# PTFV_GECKO_SNSR.net
KiCad netlist of a schematic drawn in Altium Designer
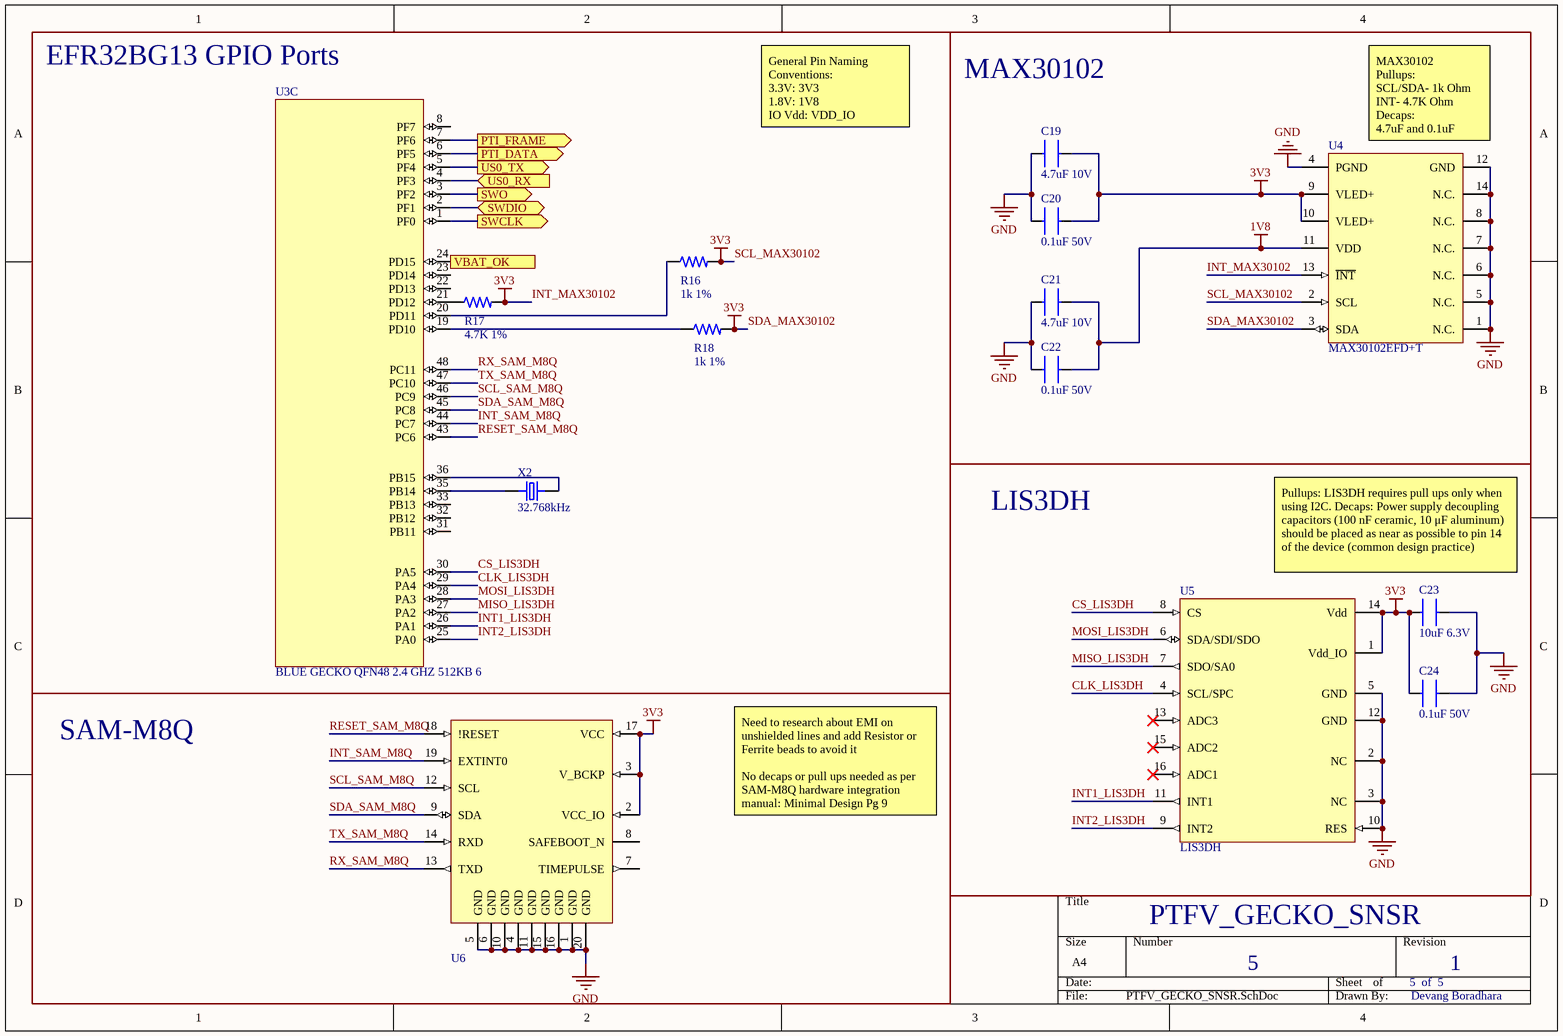
[diagram p0: PTFV_GECKO_SNSR.SchDoc]

(export (version "E")
  (design (tool "Eeschema 10.0.6"))
  (components
    (comp (ref "C19")
      (value "4.7uF 10V")
      (footprint "CAP_0603_1MM")
      (description "CAP CER 4.7UF 10V X5R 0603")
      (fields
        (field (name "MANUFACTURER") "Samsung")
        (field (name "MANUFACTURER PART NUMBER") "CL10A475KP8NNNC")
      )
      (libsource (lib "LPEDT_Parts") (part "CL10A475KP8NNNC"))
    )
    (comp (ref "C20")
      (value "0.1uF 50V")
      (footprint "CAP_0603_1MM")
      (description "CAP CER 0.1UF 50V X5R 0603")
      (fields
        (field (name "MANUFACTURER") "Yageo")
        (field (name "MANUFACTURER PART NUMBER") "CC0603KRX5R9BB104")
      )
      (libsource (lib "LPEDT_Parts") (part "CC0603KRX5R9BB104"))
    )
    (comp (ref "C21")
      (value "4.7uF 10V")
      (footprint "CAP_0603_1MM")
      (description "CAP CER 4.7UF 10V X5R 0603")
      (fields
        (field (name "MANUFACTURER") "Samsung")
        (field (name "MANUFACTURER PART NUMBER") "CL10A475KP8NNNC")
      )
      (libsource (lib "LPEDT_Parts") (part "CL10A475KP8NNNC"))
    )
    (comp (ref "C22")
      (value "0.1uF 50V")
      (footprint "CAP_0603_1MM")
      (description "CAP CER 0.1UF 50V X5R 0603")
      (fields
        (field (name "MANUFACTURER") "Yageo")
        (field (name "MANUFACTURER PART NUMBER") "CC0603KRX5R9BB104")
      )
      (libsource (lib "LPEDT_Parts") (part "CC0603KRX5R9BB104"))
    )
    (comp (ref "C23")
      (value "10uF 6.3V")
      (footprint "CAP_0603_1MM")
      (description "CAP CER 10UF 6.3V X5R 0603")
      (fields
        (field (name "MANUFACTURER") "Samsung")
        (field (name "MANUFACTURER PART NUMBER") "CL10A106MQ8NNNC")
      )
      (libsource (lib "LPEDT_Parts") (part "CL10A106MQ8NNNC"))
    )
    (comp (ref "C24")
      (value "0.1uF 50V")
      (footprint "CAP_0603_1MM")
      (description "CAP CER 0.1UF 50V X5R 0603")
      (fields
        (field (name "MANUFACTURER") "Yageo")
        (field (name "MANUFACTURER PART NUMBER") "CC0603KRX5R9BB104")
      )
      (libsource (lib "LPEDT_Parts") (part "CC0603KRX5R9BB104"))
    )
    (comp (ref "R16")
      (value "1k 1%")
      (footprint "RES_0603_1608X06")
      (description "RES SMD 1k OHM 1% 1/10W 0603")
      (fields
        (field (name "MANUFACTURER") "Yageo")
        (field (name "MANUFACTURER PART NUMBER") "RC0603FR-071KL")
      )
      (libsource (lib "LPEDT_Parts_Library") (part "RC0603FR-071KL"))
    )
    (comp (ref "R17")
      (value "4.7K 1%")
      (footprint "RES_0603_1608X06")
      (description "RES SMD 4.7K OHM 1% 1/10W 0603")
      (fields
        (field (name "MANUFACTURER") "Stackpole Electronics")
        (field (name "MANUFACTURER PART NUMBER") "RMCF0603FT4K70")
      )
      (libsource (lib "LPEDT_Parts_Library") (part "RMCF0603FT4K70"))
    )
    (comp (ref "R18")
      (value "1k 1%")
      (footprint "RES_0603_1608X06")
      (description "RES SMD 1k OHM 1% 1/10W 0603")
      (fields
        (field (name "MANUFACTURER") "Yageo")
        (field (name "MANUFACTURER PART NUMBER") "RC0603FR-071KL")
      )
      (libsource (lib "LPEDT_Parts_Library") (part "RC0603FR-071KL"))
    )
    (comp (ref "U3")
      (value "BLUE GECKO QFN48 2.4 GHZ 512KB 6")
      (footprint "QFN_48_7X7")
      (description "Blue Gecko BLE Soc QFN48 2.4 G 10 dB BLE/Proprietary 512 kB 64 kB(RAM) 31GPIO")
      (fields
        (field (name "MANUFACTURER") "Silicon Labs")
        (field (name "MANUFACTURER PART NUMBER") "EFR32BG13P632F512GM48-DR")
      )
      (libsource (lib "LPEDT_Parts_Library") (part "EFR32BG13P632F512GM48-DR"))
    )
    (comp (ref "U4")
      (value "MAX30102EFD+T")
      (footprint "14_SON_SPO2")
      (description "SENSOR OXIMETER/HEART RATE I2C")
      (fields (field (name "MANUFACTURER") "Maxim"))
      (libsource (lib "LPEDT_Parts") (part "MAX30102EFD+T"))
    )
    (comp (ref "U5")
      (value "LIS3DH")
      (footprint "16_QFN_LIS3DH")
      (libsource (lib "LPEDT_Parts_Library") (part "LIS3DH"))
    )
    (comp (ref "U6")
      (value "GPS_SAM-M8Q")
      (footprint "20_QFN_SAM_M8Q")
      (description "RF Receiver Galileo, GLONASS, GPS 1.575GHz, 1.602GHz -165dBm 400kbps On-Board, Patch Module")
      (fields (field (name "MANUFACTURER") "u-blox") (field (name "MANUFACTURER PART NUMBER") "SAM-M8Q-0"))
      (libsource (lib "LPEDT_Parts_Library") (part "SAM-M8Q-0-10"))
    )
    (comp (ref "X2")
      (value "32.768kHz")
      (footprint "XTAL_ECS-.327-7-34B-TR")
      (description "32.768kHz Â±20ppm Crystal 7pF 70 kOhms 2-SMD, No Lead")
      (fields (field (name "MP") "ECS-.327-7-34B-TR") (field (name "MF") "ECS Inc."))
      (libsource (lib "LPEDT_Parts_Library") (part "ECS-.327-7-34B-TR"))
    )
  )
  (nets
    (net (code "1") (name "/CLK_LIS3DH") (class "Default")
      (node (ref "U3") (pin "29") (pinfunction "PA4_29") (pintype "bidirectional"))
      (node (ref "U5") (pin "4") (pinfunction "SCL/SPC_4") (pintype "input"))
    )
    (net (code "2") (name "/CS_LIS3DH") (class "Default")
      (node (ref "U3") (pin "30") (pinfunction "PA5_30") (pintype "bidirectional"))
      (node (ref "U5") (pin "8") (pinfunction "CS_8") (pintype "input"))
    )
    (net (code "3") (name "/INT1_LIS3DH") (class "Default")
      (node (ref "U3") (pin "26") (pinfunction "PA1_26") (pintype "bidirectional"))
      (node (ref "U5") (pin "11") (pinfunction "INT1_11") (pintype "output"))
    )
    (net (code "4") (name "/INT2_LIS3DH") (class "Default")
      (node (ref "U3") (pin "25") (pinfunction "PA0_25") (pintype "bidirectional"))
      (node (ref "U5") (pin "9") (pinfunction "INT2_9") (pintype "output"))
    )
    (net (code "5") (name "/INT_SAM_M8Q") (class "Default")
      (node (ref "U3") (pin "44") (pinfunction "PC7_44") (pintype "bidirectional"))
      (node (ref "U6") (pin "19") (pinfunction "EXTINT0_19") (pintype "input"))
    )
    (net (code "6") (name "/MISO_LIS3DH") (class "Default")
      (node (ref "U3") (pin "27") (pinfunction "PA2_27") (pintype "bidirectional"))
      (node (ref "U5") (pin "7") (pinfunction "SDO/SA0_7") (pintype "output"))
    )
    (net (code "7") (name "/MOSI_LIS3DH") (class "Default")
      (node (ref "U3") (pin "28") (pinfunction "PA3_28") (pintype "bidirectional"))
      (node (ref "U5") (pin "6") (pinfunction "SDA/SDI/SDO_6") (pintype "bidirectional"))
    )
    (net (code "8") (name "/PTI_DATA") (class "Default")
      (node (ref "U3") (pin "6") (pinfunction "PF5_6") (pintype "bidirectional"))
    )
    (net (code "9") (name "/PTI_FRAME") (class "Default")
      (node (ref "U3") (pin "7") (pinfunction "PF6_7") (pintype "bidirectional"))
    )
    (net (code "10") (name "/RESET_SAM_M8Q") (class "Default")
      (node (ref "U3") (pin "43") (pinfunction "PC6_43") (pintype "bidirectional"))
      (node (ref "U6") (pin "18") (pinfunction "!RESET_18") (pintype "input"))
    )
    (net (code "11") (name "/RX_SAM_M8Q") (class "Default")
      (node (ref "U3") (pin "48") (pinfunction "PC11_48") (pintype "bidirectional"))
      (node (ref "U6") (pin "13") (pinfunction "TXD_13") (pintype "output"))
    )
    (net (code "12") (name "/SCL_SAM_M8Q") (class "Default")
      (node (ref "U3") (pin "46") (pinfunction "PC9_46") (pintype "bidirectional"))
      (node (ref "U6") (pin "12") (pinfunction "SCL_12") (pintype "input"))
    )
    (net (code "13") (name "/SDA_SAM_M8Q") (class "Default")
      (node (ref "U3") (pin "45") (pinfunction "PC8_45") (pintype "bidirectional"))
      (node (ref "U6") (pin "9") (pinfunction "SDA_9") (pintype "bidirectional"))
    )
    (net (code "14") (name "/SWCLK") (class "Default")
      (node (ref "U3") (pin "1") (pinfunction "PF0_1") (pintype "bidirectional"))
    )
    (net (code "15") (name "/SWDIO") (class "Default")
      (node (ref "U3") (pin "2") (pinfunction "PF1_2") (pintype "bidirectional"))
    )
    (net (code "16") (name "/SWO") (class "Default")
      (node (ref "U3") (pin "3") (pinfunction "PF2_3") (pintype "bidirectional"))
    )
    (net (code "17") (name "/TX_SAM_M8Q") (class "Default")
      (node (ref "U3") (pin "47") (pinfunction "PC10_47") (pintype "bidirectional"))
      (node (ref "U6") (pin "14") (pinfunction "RXD_14") (pintype "input"))
    )
    (net (code "18") (name "/US0_RX") (class "Default")
      (node (ref "U3") (pin "4") (pinfunction "PF3_4") (pintype "bidirectional"))
    )
    (net (code "19") (name "/US0_TX") (class "Default")
      (node (ref "U3") (pin "5") (pinfunction "PF4_5") (pintype "bidirectional"))
    )
    (net (code "20") (name "/VBAT_OK") (class "Default")
      (node (ref "U3") (pin "24") (pinfunction "PD15_24") (pintype "bidirectional"))
    )
    (net (code "21") (name "1V8") (class "Default")
      (node (ref "C21") (pin "1") (pinfunction "1_1") (pintype "passive"))
      (node (ref "C22") (pin "1") (pinfunction "1_1") (pintype "passive"))
      (node (ref "U4") (pin "11") (pinfunction "VDD_11") (pintype "power_in"))
    )
    (net (code "22") (name "3V3") (class "Default")
      (node (ref "C19") (pin "1") (pinfunction "1_1") (pintype "passive"))
      (node (ref "C20") (pin "1") (pinfunction "1_1") (pintype "passive"))
      (node (ref "C23") (pin "2") (pinfunction "2_2") (pintype "passive"))
      (node (ref "C24") (pin "2") (pinfunction "2_2") (pintype "passive"))
      (node (ref "R16") (pin "2") (pinfunction "2_2") (pintype "passive"))
      (node (ref "R17") (pin "2") (pinfunction "2_2") (pintype "passive"))
      (node (ref "R18") (pin "2") (pinfunction "2_2") (pintype "passive"))
      (node (ref "U4") (pin "10") (pinfunction "VLED+_10") (pintype "power_in"))
      (node (ref "U4") (pin "13") (pinfunction "~{INT}_13") (pintype "input"))
      (node (ref "U4") (pin "2") (pinfunction "SCL_2") (pintype "input"))
      (node (ref "U4") (pin "3") (pinfunction "SDA_3") (pintype "bidirectional"))
      (node (ref "U4") (pin "9") (pinfunction "VLED+_9") (pintype "power_in"))
      (node (ref "U5") (pin "1") (pinfunction "Vdd_IO_1") (pintype "power_in"))
      (node (ref "U5") (pin "14") (pinfunction "Vdd_14") (pintype "power_in"))
      (node (ref "U6") (pin "17") (pinfunction "VCC_17") (pintype "input"))
      (node (ref "U6") (pin "2") (pinfunction "VCC_IO_2") (pintype "input"))
      (node (ref "U6") (pin "3") (pinfunction "V_BCKP_3") (pintype "input"))
    )
    (net (code "23") (name "GND") (class "Default")
      (node (ref "C19") (pin "2") (pinfunction "2_2") (pintype "passive"))
      (node (ref "C20") (pin "2") (pinfunction "2_2") (pintype "passive"))
      (node (ref "C21") (pin "2") (pinfunction "2_2") (pintype "passive"))
      (node (ref "C22") (pin "2") (pinfunction "2_2") (pintype "passive"))
      (node (ref "C23") (pin "1") (pinfunction "1_1") (pintype "passive"))
      (node (ref "C24") (pin "1") (pinfunction "1_1") (pintype "passive"))
      (node (ref "U4") (pin "1") (pinfunction "N.C._1") (pintype "passive"))
      (node (ref "U4") (pin "12") (pinfunction "GND_12") (pintype "power_in"))
      (node (ref "U4") (pin "14") (pinfunction "N.C._14") (pintype "passive"))
      (node (ref "U4") (pin "4") (pinfunction "PGND_4") (pintype "power_in"))
      (node (ref "U4") (pin "5") (pinfunction "N.C._5") (pintype "passive"))
      (node (ref "U4") (pin "6") (pinfunction "N.C._6") (pintype "passive"))
      (node (ref "U4") (pin "7") (pinfunction "N.C._7") (pintype "passive"))
      (node (ref "U4") (pin "8") (pinfunction "N.C._8") (pintype "passive"))
      (node (ref "U5") (pin "10") (pinfunction "RES_10") (pintype "input"))
      (node (ref "U5") (pin "12") (pinfunction "GND_12") (pintype "power_in"))
      (node (ref "U5") (pin "2") (pinfunction "NC_2") (pintype "passive"))
      (node (ref "U5") (pin "3") (pinfunction "NC_3") (pintype "passive"))
      (node (ref "U5") (pin "5") (pinfunction "GND_5") (pintype "power_in"))
      (node (ref "U6") (pin "1") (pinfunction "GND_1") (pintype "passive"))
      (node (ref "U6") (pin "10") (pinfunction "GND_10") (pintype "passive"))
      (node (ref "U6") (pin "11") (pinfunction "GND_11") (pintype "passive"))
      (node (ref "U6") (pin "15") (pinfunction "GND_15") (pintype "passive"))
      (node (ref "U6") (pin "16") (pinfunction "GND_16") (pintype "passive"))
      (node (ref "U6") (pin "20") (pinfunction "GND_20") (pintype "passive"))
      (node (ref "U6") (pin "4") (pinfunction "GND_4") (pintype "passive"))
      (node (ref "U6") (pin "5") (pinfunction "GND_5") (pintype "passive"))
      (node (ref "U6") (pin "6") (pinfunction "GND_6") (pintype "passive"))
    )
    (net (code "24") (name "Net-(U3C-PB14)") (class "Default")
      (node (ref "U3") (pin "35") (pinfunction "PB14_35") (pintype "bidirectional"))
      (node (ref "X2") (pin "1") (pinfunction "1_1") (pintype "passive"))
    )
    (net (code "25") (name "Net-(U3C-PB15)") (class "Default")
      (node (ref "U3") (pin "36") (pinfunction "PB15_36") (pintype "bidirectional"))
      (node (ref "X2") (pin "2") (pinfunction "2_2") (pintype "passive"))
    )
    (net (code "26") (name "Net-(U3C-PD10)") (class "Default")
      (node (ref "R18") (pin "1") (pinfunction "1_1") (pintype "passive"))
      (node (ref "U3") (pin "19") (pinfunction "PD10_19") (pintype "bidirectional"))
    )
    (net (code "27") (name "Net-(U3C-PD11)") (class "Default")
      (node (ref "R16") (pin "1") (pinfunction "1_1") (pintype "passive"))
      (node (ref "U3") (pin "20") (pinfunction "PD11_20") (pintype "bidirectional"))
    )
    (net (code "28") (name "Net-(U3C-PD12)") (class "Default")
      (node (ref "R17") (pin "1") (pinfunction "1_1") (pintype "passive"))
      (node (ref "U3") (pin "21") (pinfunction "PD12_21") (pintype "bidirectional"))
    )
    (net (code "29") (name "unconnected-(U3C-PB11-Pad31)") (class "Default")
      (node (ref "U3") (pin "31") (pinfunction "PB11_31") (pintype "bidirectional"))
    )
    (net (code "30") (name "unconnected-(U3C-PB12-Pad32)") (class "Default")
      (node (ref "U3") (pin "32") (pinfunction "PB12_32") (pintype "bidirectional"))
    )
    (net (code "31") (name "unconnected-(U3C-PB13-Pad33)") (class "Default")
      (node (ref "U3") (pin "33") (pinfunction "PB13_33") (pintype "bidirectional"))
    )
    (net (code "32") (name "unconnected-(U3C-PD13-Pad22)") (class "Default")
      (node (ref "U3") (pin "22") (pinfunction "PD13_22") (pintype "bidirectional"))
    )
    (net (code "33") (name "unconnected-(U3C-PD14-Pad23)") (class "Default")
      (node (ref "U3") (pin "23") (pinfunction "PD14_23") (pintype "bidirectional"))
    )
    (net (code "34") (name "unconnected-(U3C-PF7-Pad8)") (class "Default")
      (node (ref "U3") (pin "8") (pinfunction "PF7_8") (pintype "bidirectional"))
    )
    (net (code "35") (name "unconnected-(U5-ADC1-Pad16)") (class "Default")
      (node (ref "U5") (pin "16") (pinfunction "ADC1_16") (pintype "input+no_connect"))
    )
    (net (code "36") (name "unconnected-(U5-ADC2-Pad15)") (class "Default")
      (node (ref "U5") (pin "15") (pinfunction "ADC2_15") (pintype "input+no_connect"))
    )
    (net (code "37") (name "unconnected-(U5-ADC3-Pad13)") (class "Default")
      (node (ref "U5") (pin "13") (pinfunction "ADC3_13") (pintype "input+no_connect"))
    )
    (net (code "38") (name "unconnected-(U6-SAFEBOOT_N-Pad8)") (class "Default")
      (node (ref "U6") (pin "8") (pinfunction "SAFEBOOT_N_8") (pintype "passive"))
    )
    (net (code "39") (name "unconnected-(U6-TIMEPULSE-Pad7)") (class "Default")
      (node (ref "U6") (pin "7") (pinfunction "TIMEPULSE_7") (pintype "output"))
    )
  )
)
